# CPU.net
KiCad netlist of a schematic drawn in Altium Designer
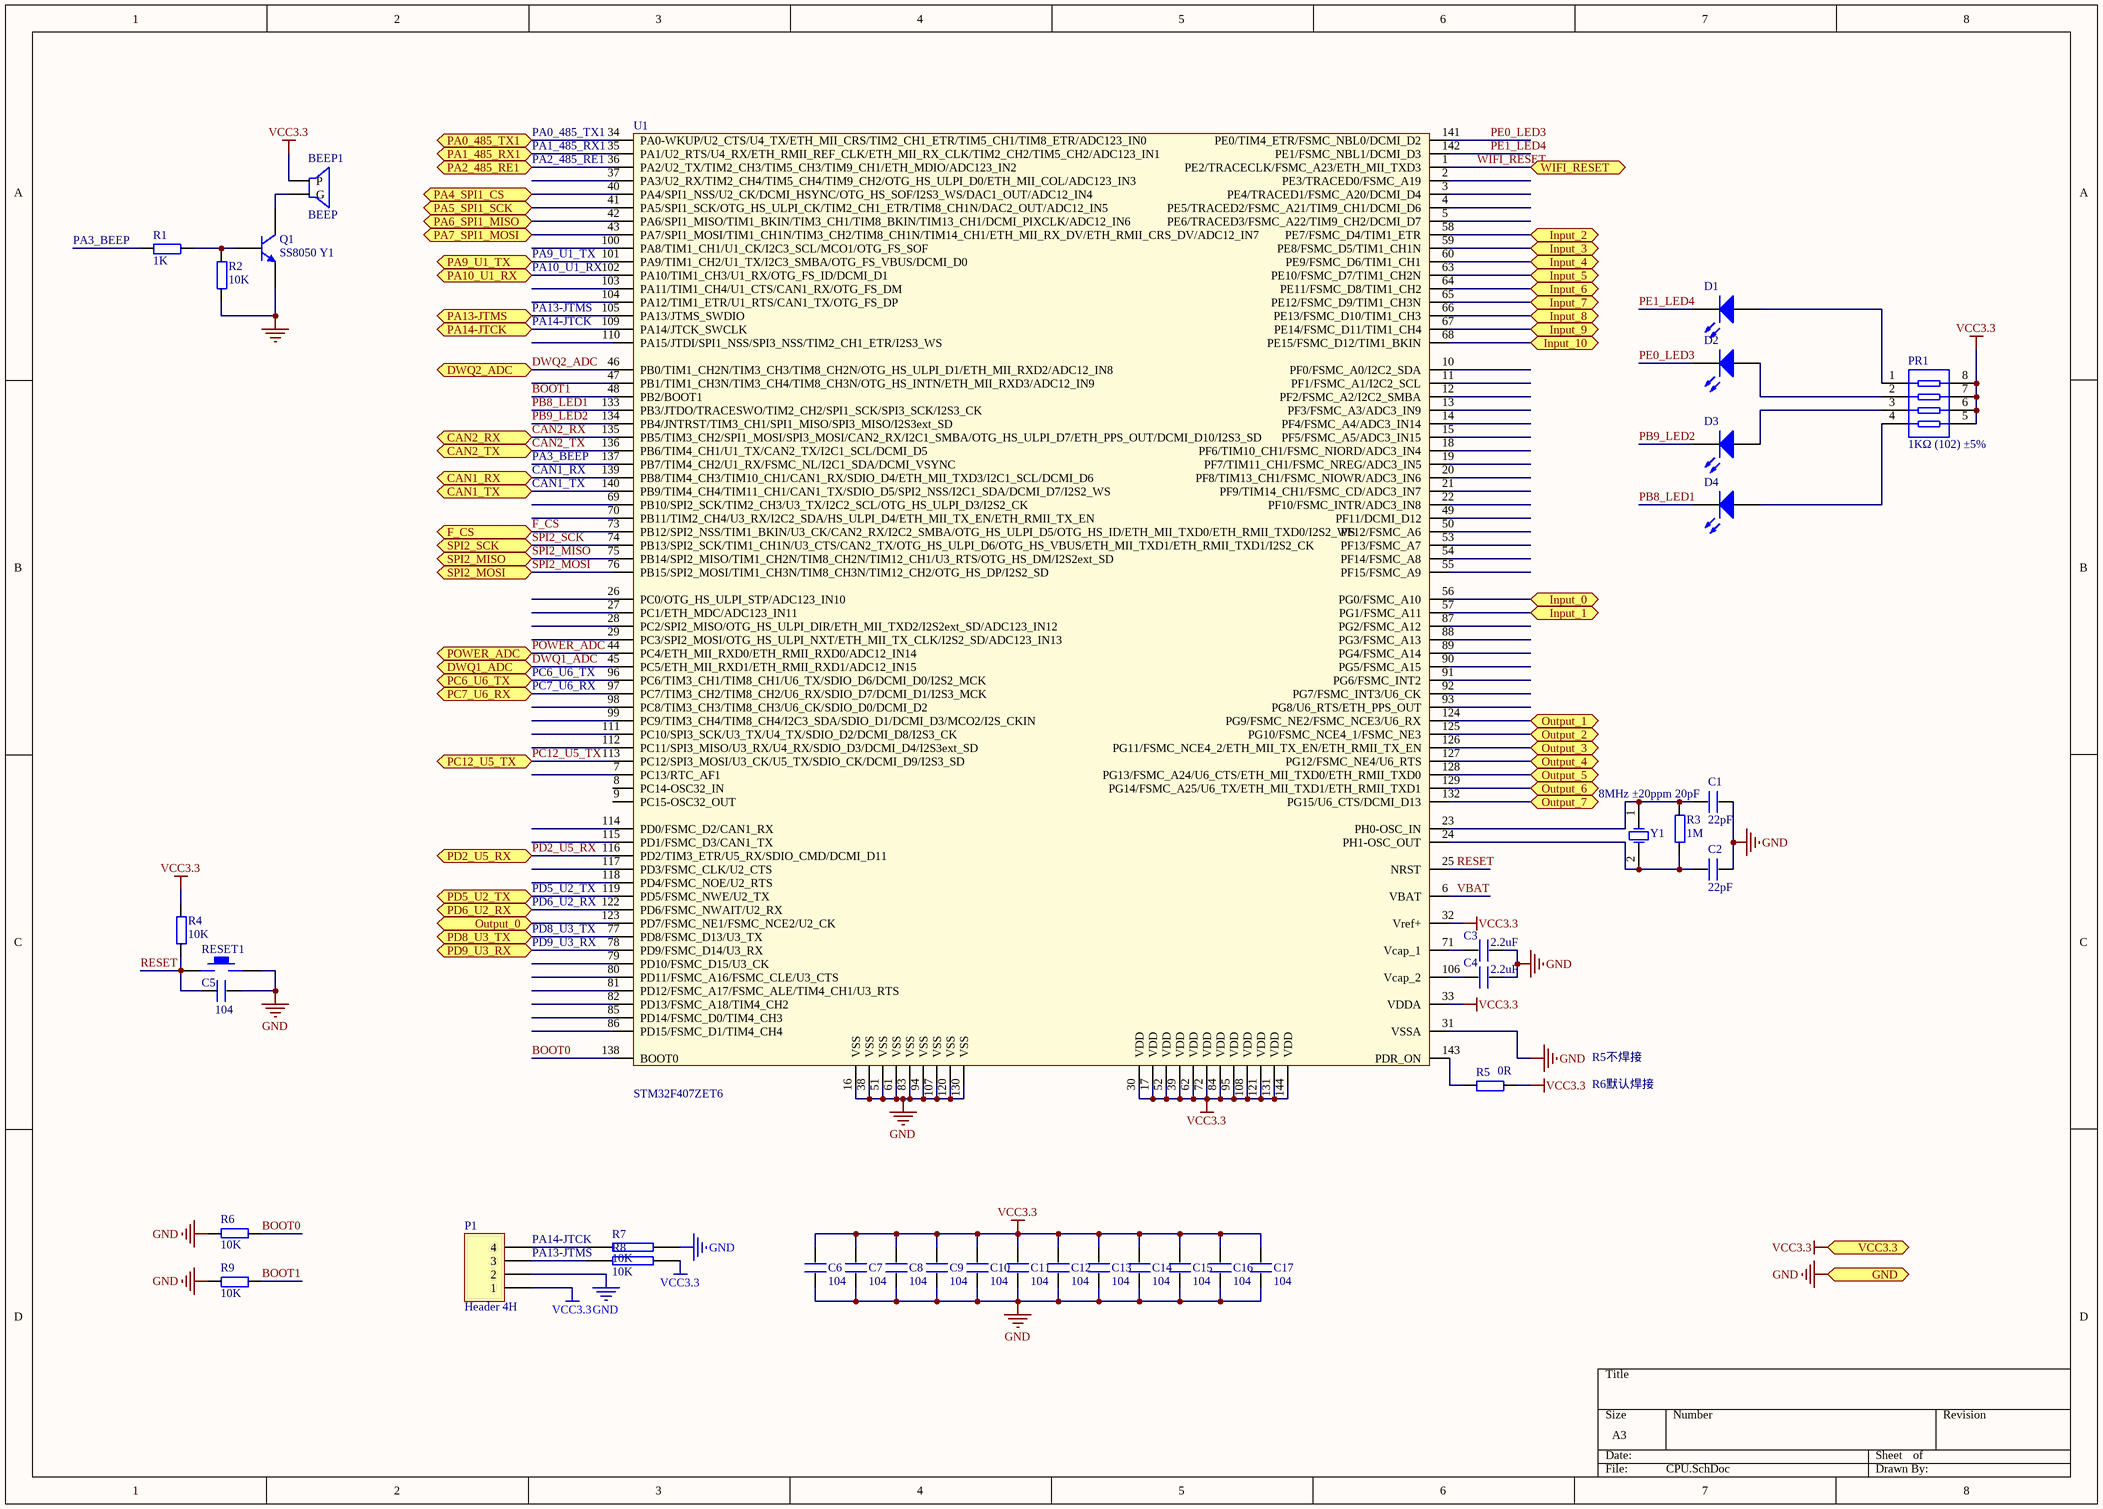
[diagram p0: CPU.SchDoc]

(export (version "E")
  (design (tool "Eeschema 10.0.6"))
  (components
    (comp (ref "BEEP1") (value "BEEP") (footprint "BELL-5") (libsource (lib "WarShip V3_SCH") (part "BEEP")))
    (comp (ref "C1")
      (value "22pF")
      (footprint "0603_C")
      (libsource (lib "Explorer STM32F407封装库") (part "C_3"))
    )
    (comp (ref "C2")
      (value "22pF")
      (footprint "0603_C")
      (libsource (lib "Explorer STM32F407封装库") (part "C_3"))
    )
    (comp (ref "C3")
      (value "2.2uF")
      (footprint "0603_C")
      (libsource (lib "Explorer STM32F407封装库") (part "C"))
    )
    (comp (ref "C4")
      (value "2.2uF")
      (footprint "0603_C")
      (libsource (lib "Explorer STM32F407封装库") (part "C"))
    )
    (comp (ref "C5") (value "104") (footprint "0603_C") (libsource (lib "Explorer STM32F407封装库") (part "C")))
    (comp (ref "C6") (value "104") (footprint "0603_C") (libsource (lib "WarShip V3_SCH") (part "C")))
    (comp (ref "C7") (value "104") (footprint "0603_C") (libsource (lib "WarShip V3_SCH") (part "C")))
    (comp (ref "C8") (value "104") (footprint "0603_C") (libsource (lib "WarShip V3_SCH") (part "C")))
    (comp (ref "C9") (value "104") (footprint "0603_C") (libsource (lib "WarShip V3_SCH") (part "C")))
    (comp (ref "C10") (value "104") (footprint "0603_C") (libsource (lib "WarShip V3_SCH") (part "C")))
    (comp (ref "C11") (value "104") (footprint "0603_C") (libsource (lib "WarShip V3_SCH") (part "C")))
    (comp (ref "C12") (value "104") (footprint "0603_C") (libsource (lib "WarShip V3_SCH") (part "C")))
    (comp (ref "C13") (value "104") (footprint "0603_C") (libsource (lib "WarShip V3_SCH") (part "C")))
    (comp (ref "C14") (value "104") (footprint "0603_C") (libsource (lib "WarShip V3_SCH") (part "C")))
    (comp (ref "C15") (value "104") (footprint "0603_C") (libsource (lib "WarShip V3_SCH") (part "C")))
    (comp (ref "C16") (value "104") (footprint "0603_C") (libsource (lib "WarShip V3_SCH") (part "C")))
    (comp (ref "C17") (value "104") (footprint "0603_C") (libsource (lib "WarShip V3_SCH") (part "C")))
    (comp (ref "D1")
      (value "红灯 0805")
      (footprint "LC-0805_LED_S1")
      (description "Typical INFRARED GaAs LED")
      (fields (field (name "PUBLISHER") "Altium Limited"))
      (libsource (lib "继电器板_1") (part "LED0"))
    )
    (comp (ref "D2")
      (value "红灯 0805")
      (footprint "LC-0805_LED_S1")
      (description "Typical INFRARED GaAs LED")
      (fields (field (name "PUBLISHER") "Altium Limited"))
      (libsource (lib "继电器板_1") (part "LED0"))
    )
    (comp (ref "D3")
      (value "红灯 0805")
      (footprint "LC-0805_LED_S1")
      (description "Typical INFRARED GaAs LED")
      (fields (field (name "PUBLISHER") "Altium Limited"))
      (libsource (lib "继电器板_1") (part "LED0"))
    )
    (comp (ref "D4")
      (value "红灯 0805")
      (footprint "LC-0805_LED_S1")
      (description "Typical INFRARED GaAs LED")
      (fields (field (name "PUBLISHER") "Altium Limited"))
      (libsource (lib "继电器板_1") (part "LED0"))
    )
    (comp (ref "P1")
      (value "Header 4H")
      (footprint "IDE4")
      (description "Header, 4-Pin, Right Angle")
      (fields (field (name "PUBLISHER") "Altium Limited"))
      (libsource (lib "Miscellaneous Connectors") (part "Header 4H"))
    )
    (comp (ref "PR1")
      (value "1KΩ (102) ±5%")
      (footprint "0603_Rx4")
      (description "贴片排阻")
      (libsource (lib "Miscellaneous Devices LC") (part "0603*4  1KΩ (102) 5%"))
    )
    (comp (ref "Q1")
      (value "SS8050 Y1")
      (footprint "SOT-23(SOT-23-3)")
      (description "三极管")
      (libsource (lib "Miscellaneous Devices LC") (part "SOT-23 SS8050 Y1"))
    )
    (comp (ref "R1") (value "1K") (footprint "0603_R") (libsource (lib "WarShip V3_SCH") (part "R")))
    (comp (ref "R2") (value "10K") (footprint "0603_R") (libsource (lib "WarShip V3_SCH") (part "R")))
    (comp (ref "R3") (value "1M") (footprint "0603_R") (libsource (lib "Explorer STM32F407封装库") (part "R")))
    (comp (ref "R4")
      (value "10K")
      (footprint "0603_R")
      (libsource (lib "Explorer STM32F407封装库") (part "R_2"))
    )
    (comp (ref "R5") (value "0R") (footprint "0603_R") (libsource (lib "Explorer STM32F407封装库") (part "R_2")))
    (comp (ref "R6")
      (value "10K")
      (footprint "0603_R")
      (libsource (lib "Explorer STM32F407封装库") (part "R_1"))
    )
    (comp (ref "R7") (value "10K") (footprint "0603_R") (libsource (lib "*") (part "RES2")))
    (comp (ref "R8") (value "10K") (footprint "0603_R") (libsource (lib "*") (part "RES2")))
    (comp (ref "R9")
      (value "10K")
      (footprint "0603_R")
      (libsource (lib "Explorer STM32F407封装库") (part "R_1"))
    )
    (comp (ref "RESET1")
      (value "KEY_M")
      (footprint "SW_PB2_A1")
      (libsource (lib "Explorer STM32F407封装库") (part "KEY_M"))
    )
    (comp (ref "U1")
      (value "STM32F407ZET6")
      (footprint "LQFP-144_20x20x05P")
      (libsource (lib "Explorer STM32F407封装库") (part "STM32F407ZET6"))
    )
    (comp (ref "Y1")
      (value "8MHz ±20ppm 20pF")
      (footprint "SMD-5032_2P")
      (description "贴片晶振")
      (libsource (lib "Miscellaneous Devices LC") (part "SMD-5032_2P 8MHz 20ppm 20pF"))
    )
  )
  (nets
    (net (code "1") (name "/BOOT0") (class "Default")
      (node (ref "R6") (pin "1") (pintype "passive"))
      (node (ref "U1") (pin "138") (pinfunction "BOOT0_138") (pintype "passive"))
    )
    (net (code "2") (name "/BOOT1") (class "Default")
      (node (ref "R9") (pin "2") (pintype "passive"))
      (node (ref "U1") (pin "48") (pinfunction "PB2/BOOT1_48") (pintype "passive"))
    )
    (net (code "3") (name "/CAN1_RX") (class "Default")
      (node (ref "U1") (pin "139") (pinfunction "PB8/TIM4_CH3/TIM10_CH1/CAN1_RX/SDIO_D4/ETH_MII_TXD3/I2C1_SCL/DCMI_D6_139") (pintype "passive"))
    )
    (net (code "4") (name "/CAN1_TX") (class "Default")
      (node (ref "U1") (pin "140") (pinfunction "PB9/TIM4_CH4/TIM11_CH1/CAN1_TX/SDIO_D5/SPI2_NSS/I2C1_SDA/DCMI_D7/I2S2_WS_140") (pintype "passive"))
    )
    (net (code "5") (name "/CAN2_RX") (class "Default")
      (node (ref "U1") (pin "135") (pinfunction "PB5/TIM3_CH2/SPI1_MOSI/SPI3_MOSI/CAN2_RX/I2C1_SMBA/OTG_HS_ULPI_D7/ETH_PPS_OUT/DCMI_D10/I2S3_SD_135") (pintype "passive"))
    )
    (net (code "6") (name "/CAN2_TX") (class "Default")
      (node (ref "U1") (pin "136") (pinfunction "PB6/TIM4_CH1/U1_TX/CAN2_TX/I2C1_SCL/DCMI_D5_136") (pintype "passive"))
    )
    (net (code "7") (name "/DWQ1_ADC") (class "Default")
      (node (ref "U1") (pin "45") (pinfunction "PC5/ETH_MII_RXD1/ETH_RMII_RXD1/ADC12_IN15_45") (pintype "passive"))
    )
    (net (code "8") (name "/DWQ2_ADC") (class "Default")
      (node (ref "U1") (pin "46") (pinfunction "PB0/TIM1_CH2N/TIM3_CH3/TIM8_CH2N/OTG_HS_ULPI_D1/ETH_MII_RXD2/ADC12_IN8_46") (pintype "passive"))
    )
    (net (code "9") (name "/F_CS") (class "Default")
      (node (ref "U1") (pin "73") (pinfunction "PB12/SPI2_NSS/TIM1_BKIN/U3_CK/CAN2_RX/I2C2_SMBA/OTG_HS_ULPI_D5/OTG_HS_ID/ETH_MII_TXD0/ETH_RMII_TXD0/I2S2_WS_73") (pintype "passive"))
    )
    (net (code "10") (name "/Input_0") (class "Default")
      (node (ref "U1") (pin "56") (pinfunction "PG0/FSMC_A10_56") (pintype "passive"))
    )
    (net (code "11") (name "/Input_1") (class "Default")
      (node (ref "U1") (pin "57") (pinfunction "PG1/FSMC_A11_57") (pintype "passive"))
    )
    (net (code "12") (name "/Input_2") (class "Default")
      (node (ref "U1") (pin "58") (pinfunction "PE7/FSMC_D4/TIM1_ETR_58") (pintype "passive"))
    )
    (net (code "13") (name "/Input_3") (class "Default")
      (node (ref "U1") (pin "59") (pinfunction "PE8/FSMC_D5/TIM1_CH1N_59") (pintype "passive"))
    )
    (net (code "14") (name "/Input_4") (class "Default")
      (node (ref "U1") (pin "60") (pinfunction "PE9/FSMC_D6/TIM1_CH1_60") (pintype "passive"))
    )
    (net (code "15") (name "/Input_5") (class "Default")
      (node (ref "U1") (pin "63") (pinfunction "PE10/FSMC_D7/TIM1_CH2N_63") (pintype "passive"))
    )
    (net (code "16") (name "/Input_6") (class "Default")
      (node (ref "U1") (pin "64") (pinfunction "PE11/FSMC_D8/TIM1_CH2_64") (pintype "passive"))
    )
    (net (code "17") (name "/Input_7") (class "Default")
      (node (ref "U1") (pin "65") (pinfunction "PE12/FSMC_D9/TIM1_CH3N_65") (pintype "passive"))
    )
    (net (code "18") (name "/Input_8") (class "Default")
      (node (ref "U1") (pin "66") (pinfunction "PE13/FSMC_D10/TIM1_CH3_66") (pintype "passive"))
    )
    (net (code "19") (name "/Input_9") (class "Default")
      (node (ref "U1") (pin "67") (pinfunction "PE14/FSMC_D11/TIM1_CH4_67") (pintype "passive"))
    )
    (net (code "20") (name "/Input_10") (class "Default")
      (node (ref "U1") (pin "68") (pinfunction "PE15/FSMC_D12/TIM1_BKIN_68") (pintype "passive"))
    )
    (net (code "21") (name "/Output_0") (class "Default")
      (node (ref "U1") (pin "123") (pinfunction "PD7/FSMC_NE1/FSMC_NCE2/U2_CK_123") (pintype "passive"))
    )
    (net (code "22") (name "/Output_1") (class "Default")
      (node (ref "U1") (pin "124") (pinfunction "PG9/FSMC_NE2/FSMC_NCE3/U6_RX_124") (pintype "passive"))
    )
    (net (code "23") (name "/Output_2") (class "Default")
      (node (ref "U1") (pin "125") (pinfunction "PG10/FSMC_NCE4_1/FSMC_NE3_125") (pintype "passive"))
    )
    (net (code "24") (name "/Output_3") (class "Default")
      (node (ref "U1") (pin "126") (pinfunction "PG11/FSMC_NCE4_2/ETH_MII_TX_EN/ETH_RMII_TX_EN_126") (pintype "passive"))
    )
    (net (code "25") (name "/Output_4") (class "Default")
      (node (ref "U1") (pin "127") (pinfunction "PG12/FSMC_NE4/U6_RTS_127") (pintype "passive"))
    )
    (net (code "26") (name "/Output_5") (class "Default")
      (node (ref "U1") (pin "128") (pinfunction "PG13/FSMC_A24/U6_CTS/ETH_MII_TXD0/ETH_RMII_TXD0_128") (pintype "passive"))
    )
    (net (code "27") (name "/Output_6") (class "Default")
      (node (ref "U1") (pin "129") (pinfunction "PG14/FSMC_A25/U6_TX/ETH_MII_TXD1/ETH_RMII_TXD1_129") (pintype "passive"))
    )
    (net (code "28") (name "/Output_7") (class "Default")
      (node (ref "U1") (pin "132") (pinfunction "PG15/U6_CTS/DCMI_D13_132") (pintype "passive"))
    )
    (net (code "29") (name "/PA0_485_TX1") (class "Default")
      (node (ref "U1") (pin "34") (pinfunction "PA0-WKUP/U2_CTS/U4_TX/ETH_MII_CRS/TIM2_CH1_ETR/TIM5_CH1/TIM8_ETR/ADC123_IN0_34") (pintype "passive"))
    )
    (net (code "30") (name "/PA1_485_RX1") (class "Default")
      (node (ref "U1") (pin "35") (pinfunction "PA1/U2_RTS/U4_RX/ETH_RMII_REF_CLK/ETH_MII_RX_CLK/TIM2_CH2/TIM5_CH2/ADC123_IN1_35") (pintype "passive"))
    )
    (net (code "31") (name "/PA2_485_RE1") (class "Default")
      (node (ref "U1") (pin "36") (pinfunction "PA2/U2_TX/TIM2_CH3/TIM5_CH3/TIM9_CH1/ETH_MDIO/ADC123_IN2_36") (pintype "passive"))
    )
    (net (code "32") (name "/PA3_BEEP") (class "Default")
      (node (ref "R1") (pin "1") (pintype "passive"))
      (node (ref "U1") (pin "137") (pinfunction "PB7/TIM4_CH2/U1_RX/FSMC_NL/I2C1_SDA/DCMI_VSYNC_137") (pintype "passive"))
    )
    (net (code "33") (name "/PA4_SPI1_CS") (class "Default")
      (node (ref "U1") (pin "40") (pinfunction "PA4/SPI1_NSS/U2_CK/DCMI_HSYNC/OTG_HS_SOF/I2S3_WS/DAC1_OUT/ADC12_IN4_40") (pintype "passive"))
    )
    (net (code "34") (name "/PA5_SPI1_SCK") (class "Default")
      (node (ref "U1") (pin "41") (pinfunction "PA5/SPI1_SCK/OTG_HS_ULPI_CK/TIM2_CH1_ETR/TIM8_CH1N/DAC2_OUT/ADC12_IN5_41") (pintype "passive"))
    )
    (net (code "35") (name "/PA6_SPI1_MISO") (class "Default")
      (node (ref "U1") (pin "42") (pinfunction "PA6/SPI1_MISO/TIM1_BKIN/TIM3_CH1/TIM8_BKIN/TIM13_CH1/DCMI_PIXCLK/ADC12_IN6_42") (pintype "passive"))
    )
    (net (code "36") (name "/PA7_SPI1_MOSI") (class "Default")
      (node (ref "U1") (pin "43") (pinfunction "PA7/SPI1_MOSI/TIM1_CH1N/TIM3_CH2/TIM8_CH1N/TIM14_CH1/ETH_MII_RX_DV/ETH_RMII_CRS_DV/ADC12_IN7_43") (pintype "passive"))
    )
    (net (code "37") (name "/PA9_U1_TX") (class "Default")
      (node (ref "U1") (pin "101") (pinfunction "PA9/TIM1_CH2/U1_TX/I2C3_SMBA/OTG_FS_VBUS/DCMI_D0_101") (pintype "passive"))
    )
    (net (code "38") (name "/PA10_U1_RX") (class "Default")
      (node (ref "U1") (pin "102") (pinfunction "PA10/TIM1_CH3/U1_RX/OTG_FS_ID/DCMI_D1_102") (pintype "passive"))
    )
    (net (code "39") (name "/PA13-JTMS") (class "Default")
      (node (ref "P1") (pin "3") (pinfunction "3_3") (pintype "passive"))
      (node (ref "R8") (pin "2") (pinfunction "2_2") (pintype "passive"))
      (node (ref "U1") (pin "105") (pinfunction "PA13/JTMS_SWDIO_105") (pintype "passive"))
    )
    (net (code "40") (name "/PA14-JTCK") (class "Default")
      (node (ref "P1") (pin "4") (pinfunction "4_4") (pintype "passive"))
      (node (ref "R7") (pin "2") (pinfunction "2_2") (pintype "passive"))
      (node (ref "U1") (pin "109") (pinfunction "PA14/JTCK_SWCLK_109") (pintype "passive"))
    )
    (net (code "41") (name "/PB8_LED1") (class "Default")
      (node (ref "D4") (pin "K") (pinfunction "K_K") (pintype "passive"))
      (node (ref "U1") (pin "133") (pinfunction "PB3/JTDO/TRACESWO/TIM2_CH2/SPI1_SCK/SPI3_SCK/I2S3_CK_133") (pintype "passive"))
    )
    (net (code "42") (name "/PB9_LED2") (class "Default")
      (node (ref "D3") (pin "K") (pinfunction "K_K") (pintype "passive"))
      (node (ref "U1") (pin "134") (pinfunction "PB4/JNTRST/TIM3_CH1/SPI1_MISO/SPI3_MISO/I2S3ext_SD_134") (pintype "passive"))
    )
    (net (code "43") (name "/PC6_U6_TX") (class "Default")
      (node (ref "U1") (pin "96") (pinfunction "PC6/TIM3_CH1/TIM8_CH1/U6_TX/SDIO_D6/DCMI_D0/I2S2_MCK_96") (pintype "passive"))
    )
    (net (code "44") (name "/PC7_U6_RX") (class "Default")
      (node (ref "U1") (pin "97") (pinfunction "PC7/TIM3_CH2/TIM8_CH2/U6_RX/SDIO_D7/DCMI_D1/I2S3_MCK_97") (pintype "passive"))
    )
    (net (code "45") (name "/PC12_U5_TX") (class "Default")
      (node (ref "U1") (pin "113") (pinfunction "PC12/SPI3_MOSI/U3_CK/U5_TX/SDIO_CK/DCMI_D9/I2S3_SD_113") (pintype "passive"))
    )
    (net (code "46") (name "/PD2_U5_RX") (class "Default")
      (node (ref "U1") (pin "116") (pinfunction "PD2/TIM3_ETR/U5_RX/SDIO_CMD/DCMI_D11_116") (pintype "passive"))
    )
    (net (code "47") (name "/PD5_U2_TX") (class "Default")
      (node (ref "U1") (pin "119") (pinfunction "PD5/FSMC_NWE/U2_TX_119") (pintype "passive"))
    )
    (net (code "48") (name "/PD6_U2_RX") (class "Default")
      (node (ref "U1") (pin "122") (pinfunction "PD6/FSMC_NWAIT/U2_RX_122") (pintype "passive"))
    )
    (net (code "49") (name "/PD8_U3_TX") (class "Default")
      (node (ref "U1") (pin "77") (pinfunction "PD8/FSMC_D13/U3_TX_77") (pintype "passive"))
    )
    (net (code "50") (name "/PD9_U3_RX") (class "Default")
      (node (ref "U1") (pin "78") (pinfunction "PD9/FSMC_D14/U3_RX_78") (pintype "passive"))
    )
    (net (code "51") (name "/PE0_LED3") (class "Default")
      (node (ref "D2") (pin "K") (pinfunction "K_K") (pintype "passive"))
      (node (ref "U1") (pin "141") (pinfunction "PE0/TIM4_ETR/FSMC_NBL0/DCMI_D2_141") (pintype "passive"))
    )
    (net (code "52") (name "/PE1_LED4") (class "Default")
      (node (ref "D1") (pin "K") (pinfunction "K_K") (pintype "passive"))
      (node (ref "U1") (pin "142") (pinfunction "PE1/FSMC_NBL1/DCMI_D3_142") (pintype "passive"))
    )
    (net (code "53") (name "/POWER_ADC") (class "Default")
      (node (ref "U1") (pin "44") (pinfunction "PC4/ETH_MII_RXD0/ETH_RMII_RXD0/ADC12_IN14_44") (pintype "passive"))
    )
    (net (code "54") (name "/RESET") (class "Default")
      (node (ref "C5") (pin "1") (pintype "passive"))
      (node (ref "R4") (pin "1") (pintype "passive"))
      (node (ref "RESET1") (pin "1") (pinfunction "1_1") (pintype "passive"))
      (node (ref "U1") (pin "25") (pinfunction "NRST_25") (pintype "passive"))
    )
    (net (code "55") (name "/SPI2_MISO") (class "Default")
      (node (ref "U1") (pin "75") (pinfunction "PB14/SPI2_MISO/TIM1_CH2N/TIM8_CH2N/TIM12_CH1/U3_RTS/OTG_HS_DM/I2S2ext_SD_75") (pintype "passive"))
    )
    (net (code "56") (name "/SPI2_MOSI") (class "Default")
      (node (ref "U1") (pin "76") (pinfunction "PB15/SPI2_MOSI/TIM1_CH3N/TIM8_CH3N/TIM12_CH2/OTG_HS_DP/I2S2_SD_76") (pintype "passive"))
    )
    (net (code "57") (name "/SPI2_SCK") (class "Default")
      (node (ref "U1") (pin "74") (pinfunction "PB13/SPI2_SCK/TIM1_CH1N/U3_CTS/CAN2_TX/OTG_HS_ULPI_D6/OTG_HS_VBUS/ETH_MII_TXD1/ETH_RMII_TXD1/I2S2_CK_74") (pintype "passive"))
    )
    (net (code "58") (name "/VBAT") (class "Default")
      (node (ref "U1") (pin "6") (pinfunction "VBAT_6") (pintype "passive"))
    )
    (net (code "59") (name "/WIFI_RESET") (class "Default")
      (node (ref "U1") (pin "1") (pinfunction "PE2/TRACECLK/FSMC_A23/ETH_MII_TXD3_1") (pintype "passive"))
    )
    (net (code "60") (name "GND") (class "Default")
      (node (ref "C1") (pin "1") (pintype "passive"))
      (node (ref "C10") (pin "1") (pintype "passive"))
      (node (ref "C11") (pin "1") (pintype "passive"))
      (node (ref "C12") (pin "1") (pintype "passive"))
      (node (ref "C13") (pin "1") (pintype "passive"))
      (node (ref "C14") (pin "1") (pintype "passive"))
      (node (ref "C15") (pin "1") (pintype "passive"))
      (node (ref "C16") (pin "1") (pintype "passive"))
      (node (ref "C17") (pin "1") (pintype "passive"))
      (node (ref "C2") (pin "1") (pintype "passive"))
      (node (ref "C3") (pin "2") (pintype "passive"))
      (node (ref "C4") (pin "2") (pintype "passive"))
      (node (ref "C5") (pin "2") (pintype "passive"))
      (node (ref "C6") (pin "1") (pintype "passive"))
      (node (ref "C7") (pin "1") (pintype "passive"))
      (node (ref "C8") (pin "1") (pintype "passive"))
      (node (ref "C9") (pin "1") (pintype "passive"))
      (node (ref "P1") (pin "2") (pinfunction "2_2") (pintype "passive"))
      (node (ref "Q1") (pin "2") (pinfunction "E_2") (pintype "passive"))
      (node (ref "R2") (pin "1") (pintype "passive"))
      (node (ref "R6") (pin "2") (pintype "passive"))
      (node (ref "R7") (pin "1") (pinfunction "1_1") (pintype "passive"))
      (node (ref "R9") (pin "1") (pintype "passive"))
      (node (ref "RESET1") (pin "2") (pinfunction "2_2") (pintype "passive"))
      (node (ref "U1") (pin "107") (pinfunction "VSS_107") (pintype "passive"))
      (node (ref "U1") (pin "120") (pinfunction "VSS_120") (pintype "passive"))
      (node (ref "U1") (pin "130") (pinfunction "VSS_130") (pintype "passive"))
      (node (ref "U1") (pin "16") (pinfunction "VSS_16") (pintype "passive"))
      (node (ref "U1") (pin "31") (pinfunction "VSSA_31") (pintype "passive"))
      (node (ref "U1") (pin "38") (pinfunction "VSS_38") (pintype "passive"))
      (node (ref "U1") (pin "51") (pinfunction "VSS_51") (pintype "passive"))
      (node (ref "U1") (pin "61") (pinfunction "VSS_61") (pintype "passive"))
      (node (ref "U1") (pin "83") (pinfunction "VSS_83") (pintype "passive"))
      (node (ref "U1") (pin "94") (pinfunction "VSS_94") (pintype "passive"))
    )
    (net (code "61") (name "Net-(BEEP1-G)") (class "Default")
      (node (ref "BEEP1") (pin "2") (pinfunction "G_2") (pintype "passive"))
      (node (ref "Q1") (pin "3") (pinfunction "C_3") (pintype "passive"))
    )
    (net (code "62") (name "Net-(D1-PadA)") (class "Default")
      (node (ref "D1") (pin "A") (pinfunction "A_A") (pintype "passive"))
      (node (ref "PR1") (pin "1") (pinfunction "1_1") (pintype "passive"))
    )
    (net (code "63") (name "Net-(D2-PadA)") (class "Default")
      (node (ref "D2") (pin "A") (pinfunction "A_A") (pintype "passive"))
      (node (ref "PR1") (pin "2") (pinfunction "2_2") (pintype "passive"))
    )
    (net (code "64") (name "Net-(D3-PadA)") (class "Default")
      (node (ref "D3") (pin "A") (pinfunction "A_A") (pintype "passive"))
      (node (ref "PR1") (pin "3") (pinfunction "3_3") (pintype "passive"))
    )
    (net (code "65") (name "Net-(D4-PadA)") (class "Default")
      (node (ref "D4") (pin "A") (pinfunction "A_A") (pintype "passive"))
      (node (ref "PR1") (pin "4") (pinfunction "4_4") (pintype "passive"))
    )
    (net (code "66") (name "Net-(Q1-B)") (class "Default")
      (node (ref "Q1") (pin "1") (pinfunction "B_1") (pintype "passive"))
      (node (ref "R1") (pin "2") (pintype "passive"))
      (node (ref "R2") (pin "2") (pintype "passive"))
    )
    (net (code "67") (name "Net-(U1-PDR_ON)") (class "Default")
      (node (ref "R5") (pin "1") (pintype "passive"))
      (node (ref "U1") (pin "143") (pinfunction "PDR_ON_143") (pintype "passive"))
    )
    (net (code "68") (name "Net-(U1-PH0-OSC_IN)") (class "Default")
      (node (ref "C1") (pin "2") (pintype "passive"))
      (node (ref "R3") (pin "2") (pintype "passive"))
      (node (ref "U1") (pin "23") (pinfunction "PH0-OSC_IN_23") (pintype "passive"))
      (node (ref "Y1") (pin "1") (pinfunction "OSC1_1") (pintype "passive"))
    )
    (net (code "69") (name "Net-(U1-PH1-OSC_OUT)") (class "Default")
      (node (ref "C2") (pin "2") (pintype "passive"))
      (node (ref "R3") (pin "1") (pintype "passive"))
      (node (ref "U1") (pin "24") (pinfunction "PH1-OSC_OUT_24") (pintype "passive"))
      (node (ref "Y1") (pin "2") (pinfunction "OSC2_2") (pintype "passive"))
    )
    (net (code "70") (name "Net-(U1-Vcap_1)") (class "Default")
      (node (ref "C3") (pin "1") (pintype "passive"))
      (node (ref "U1") (pin "71") (pinfunction "Vcap_1_71") (pintype "passive"))
    )
    (net (code "71") (name "Net-(U1-Vcap_2)") (class "Default")
      (node (ref "C4") (pin "1") (pintype "passive"))
      (node (ref "U1") (pin "106") (pinfunction "Vcap_2_106") (pintype "passive"))
    )
    (net (code "72") (name "VCC3.3") (class "Default")
      (node (ref "BEEP1") (pin "1") (pinfunction "P_1") (pintype "passive"))
      (node (ref "C10") (pin "2") (pintype "passive"))
      (node (ref "C11") (pin "2") (pintype "passive"))
      (node (ref "C12") (pin "2") (pintype "passive"))
      (node (ref "C13") (pin "2") (pintype "passive"))
      (node (ref "C14") (pin "2") (pintype "passive"))
      (node (ref "C15") (pin "2") (pintype "passive"))
      (node (ref "C16") (pin "2") (pintype "passive"))
      (node (ref "C17") (pin "2") (pintype "passive"))
      (node (ref "C6") (pin "2") (pintype "passive"))
      (node (ref "C7") (pin "2") (pintype "passive"))
      (node (ref "C8") (pin "2") (pintype "passive"))
      (node (ref "C9") (pin "2") (pintype "passive"))
      (node (ref "P1") (pin "1") (pinfunction "1_1") (pintype "passive"))
      (node (ref "PR1") (pin "5") (pinfunction "5_5") (pintype "passive"))
      (node (ref "PR1") (pin "6") (pinfunction "6_6") (pintype "passive"))
      (node (ref "PR1") (pin "7") (pinfunction "7_7") (pintype "passive"))
      (node (ref "PR1") (pin "8") (pinfunction "8_8") (pintype "passive"))
      (node (ref "R4") (pin "2") (pintype "passive"))
      (node (ref "R5") (pin "2") (pintype "passive"))
      (node (ref "R8") (pin "1") (pinfunction "1_1") (pintype "passive"))
      (node (ref "U1") (pin "108") (pinfunction "VDD_108") (pintype "passive"))
      (node (ref "U1") (pin "121") (pinfunction "VDD_121") (pintype "passive"))
      (node (ref "U1") (pin "131") (pinfunction "VDD_131") (pintype "passive"))
      (node (ref "U1") (pin "144") (pinfunction "VDD_144") (pintype "passive"))
      (node (ref "U1") (pin "17") (pinfunction "VDD_17") (pintype "passive"))
      (node (ref "U1") (pin "30") (pinfunction "VDD_30") (pintype "passive"))
      (node (ref "U1") (pin "32") (pinfunction "Vref+_32") (pintype "passive"))
      (node (ref "U1") (pin "33") (pinfunction "VDDA_33") (pintype "passive"))
      (node (ref "U1") (pin "39") (pinfunction "VDD_39") (pintype "passive"))
      (node (ref "U1") (pin "52") (pinfunction "VDD_52") (pintype "passive"))
      (node (ref "U1") (pin "62") (pinfunction "VDD_62") (pintype "passive"))
      (node (ref "U1") (pin "72") (pinfunction "VDD_72") (pintype "passive"))
      (node (ref "U1") (pin "84") (pinfunction "VDD_84") (pintype "passive"))
      (node (ref "U1") (pin "95") (pinfunction "VDD_95") (pintype "passive"))
    )
    (net (code "73") (name "unconnected-(U1-PA3{slash}U2_RX{slash}TIM2_CH4{slash}TIM5_CH4{slash}TIM9_CH2{slash}OTG_HS_ULPI_D0{slash}ETH_MII_COL{slash}ADC123_IN3-Pad37)") (class "Default")
      (node (ref "U1") (pin "37") (pinfunction "PA3/U2_RX/TIM2_CH4/TIM5_CH4/TIM9_CH2/OTG_HS_ULPI_D0/ETH_MII_COL/ADC123_IN3_37") (pintype "passive"))
    )
    (net (code "74") (name "unconnected-(U1-PA8{slash}TIM1_CH1{slash}U1_CK{slash}I2C3_SCL{slash}MCO1{slash}OTG_FS_SOF-Pad100)") (class "Default")
      (node (ref "U1") (pin "100") (pinfunction "PA8/TIM1_CH1/U1_CK/I2C3_SCL/MCO1/OTG_FS_SOF_100") (pintype "passive"))
    )
    (net (code "75") (name "unconnected-(U1-PA11{slash}TIM1_CH4{slash}U1_CTS{slash}CAN1_RX{slash}OTG_FS_DM-Pad103)") (class "Default")
      (node (ref "U1") (pin "103") (pinfunction "PA11/TIM1_CH4/U1_CTS/CAN1_RX/OTG_FS_DM_103") (pintype "passive"))
    )
    (net (code "76") (name "unconnected-(U1-PA12{slash}TIM1_ETR{slash}U1_RTS{slash}CAN1_TX{slash}OTG_FS_DP-Pad104)") (class "Default")
      (node (ref "U1") (pin "104") (pinfunction "PA12/TIM1_ETR/U1_RTS/CAN1_TX/OTG_FS_DP_104") (pintype "passive"))
    )
    (net (code "77") (name "unconnected-(U1-PA15{slash}JTDI{slash}SPI1_NSS{slash}SPI3_NSS{slash}TIM2_CH1_ETR{slash}I2S3_WS-Pad110)") (class "Default")
      (node (ref "U1") (pin "110") (pinfunction "PA15/JTDI/SPI1_NSS/SPI3_NSS/TIM2_CH1_ETR/I2S3_WS_110") (pintype "passive"))
    )
    (net (code "78") (name "unconnected-(U1-PB1{slash}TIM1_CH3N{slash}TIM3_CH4{slash}TIM8_CH3N{slash}OTG_HS_INTN{slash}ETH_MII_RXD3{slash}ADC12_IN9-Pad47)") (class "Default")
      (node (ref "U1") (pin "47") (pinfunction "PB1/TIM1_CH3N/TIM3_CH4/TIM8_CH3N/OTG_HS_INTN/ETH_MII_RXD3/ADC12_IN9_47") (pintype "passive"))
    )
    (net (code "79") (name "unconnected-(U1-PB10{slash}SPI2_SCK{slash}TIM2_CH3{slash}U3_TX{slash}I2C2_SCL{slash}OTG_HS_ULPI_D3{slash}I2S2_CK-Pad69)") (class "Default")
      (node (ref "U1") (pin "69") (pinfunction "PB10/SPI2_SCK/TIM2_CH3/U3_TX/I2C2_SCL/OTG_HS_ULPI_D3/I2S2_CK_69") (pintype "passive"))
    )
    (net (code "80") (name "unconnected-(U1-PB11{slash}TIM2_CH4{slash}U3_RX{slash}I2C2_SDA{slash}HS_ULPI_D4{slash}ETH_MII_TX_EN{slash}ETH_RMII_TX_EN-Pad70)") (class "Default")
      (node (ref "U1") (pin "70") (pinfunction "PB11/TIM2_CH4/U3_RX/I2C2_SDA/HS_ULPI_D4/ETH_MII_TX_EN/ETH_RMII_TX_EN_70") (pintype "passive"))
    )
    (net (code "81") (name "unconnected-(U1-PC0{slash}OTG_HS_ULPI_STP{slash}ADC123_IN10-Pad26)") (class "Default")
      (node (ref "U1") (pin "26") (pinfunction "PC0/OTG_HS_ULPI_STP/ADC123_IN10_26") (pintype "passive"))
    )
    (net (code "82") (name "unconnected-(U1-PC1{slash}ETH_MDC{slash}ADC123_IN11-Pad27)") (class "Default")
      (node (ref "U1") (pin "27") (pinfunction "PC1/ETH_MDC/ADC123_IN11_27") (pintype "passive"))
    )
    (net (code "83") (name "unconnected-(U1-PC2{slash}SPI2_MISO{slash}OTG_HS_ULPI_DIR{slash}ETH_MII_TXD2{slash}I2S2ext_SD{slash}ADC123_IN12-Pad28)") (class "Default")
      (node (ref "U1") (pin "28") (pinfunction "PC2/SPI2_MISO/OTG_HS_ULPI_DIR/ETH_MII_TXD2/I2S2ext_SD/ADC123_IN12_28") (pintype "passive"))
    )
    (net (code "84") (name "unconnected-(U1-PC3{slash}SPI2_MOSI{slash}OTG_HS_ULPI_NXT{slash}ETH_MII_TX_CLK{slash}I2S2_SD{slash}ADC123_IN13-Pad29)") (class "Default")
      (node (ref "U1") (pin "29") (pinfunction "PC3/SPI2_MOSI/OTG_HS_ULPI_NXT/ETH_MII_TX_CLK/I2S2_SD/ADC123_IN13_29") (pintype "passive"))
    )
    (net (code "85") (name "unconnected-(U1-PC8{slash}TIM3_CH3{slash}TIM8_CH3{slash}U6_CK{slash}SDIO_D0{slash}DCMI_D2-Pad98)") (class "Default")
      (node (ref "U1") (pin "98") (pinfunction "PC8/TIM3_CH3/TIM8_CH3/U6_CK/SDIO_D0/DCMI_D2_98") (pintype "passive"))
    )
    (net (code "86") (name "unconnected-(U1-PC9{slash}TIM3_CH4{slash}TIM8_CH4{slash}I2C3_SDA{slash}SDIO_D1{slash}DCMI_D3{slash}MCO2{slash}I2S_CKIN-Pad99)") (class "Default")
      (node (ref "U1") (pin "99") (pinfunction "PC9/TIM3_CH4/TIM8_CH4/I2C3_SDA/SDIO_D1/DCMI_D3/MCO2/I2S_CKIN_99") (pintype "passive"))
    )
    (net (code "87") (name "unconnected-(U1-PC10{slash}SPI3_SCK{slash}U3_TX{slash}U4_TX{slash}SDIO_D2{slash}DCMI_D8{slash}I2S3_CK-Pad111)") (class "Default")
      (node (ref "U1") (pin "111") (pinfunction "PC10/SPI3_SCK/U3_TX/U4_TX/SDIO_D2/DCMI_D8/I2S3_CK_111") (pintype "passive"))
    )
    (net (code "88") (name "unconnected-(U1-PC11{slash}SPI3_MISO{slash}U3_RX{slash}U4_RX{slash}SDIO_D3{slash}DCMI_D4{slash}I2S3ext_SD-Pad112)") (class "Default")
      (node (ref "U1") (pin "112") (pinfunction "PC11/SPI3_MISO/U3_RX/U4_RX/SDIO_D3/DCMI_D4/I2S3ext_SD_112") (pintype "passive"))
    )
    (net (code "89") (name "unconnected-(U1-PC13{slash}RTC_AF1-Pad7)") (class "Default")
      (node (ref "U1") (pin "7") (pinfunction "PC13/RTC_AF1_7") (pintype "passive"))
    )
    (net (code "90") (name "unconnected-(U1-PC14-OSC32_IN-Pad8)") (class "Default")
      (node (ref "U1") (pin "8") (pinfunction "PC14-OSC32_IN_8") (pintype "passive"))
    )
    (net (code "91") (name "unconnected-(U1-PC15-OSC32_OUT-Pad9)") (class "Default")
      (node (ref "U1") (pin "9") (pinfunction "PC15-OSC32_OUT_9") (pintype "passive"))
    )
    (net (code "92") (name "unconnected-(U1-PD0{slash}FSMC_D2{slash}CAN1_RX-Pad114)") (class "Default")
      (node (ref "U1") (pin "114") (pinfunction "PD0/FSMC_D2/CAN1_RX_114") (pintype "passive"))
    )
    (net (code "93") (name "unconnected-(U1-PD1{slash}FSMC_D3{slash}CAN1_TX-Pad115)") (class "Default")
      (node (ref "U1") (pin "115") (pinfunction "PD1/FSMC_D3/CAN1_TX_115") (pintype "passive"))
    )
    (net (code "94") (name "unconnected-(U1-PD3{slash}FSMC_CLK{slash}U2_CTS-Pad117)") (class "Default")
      (node (ref "U1") (pin "117") (pinfunction "PD3/FSMC_CLK/U2_CTS_117") (pintype "passive"))
    )
    (net (code "95") (name "unconnected-(U1-PD4{slash}FSMC_NOE{slash}U2_RTS-Pad118)") (class "Default")
      (node (ref "U1") (pin "118") (pinfunction "PD4/FSMC_NOE/U2_RTS_118") (pintype "passive"))
    )
    (net (code "96") (name "unconnected-(U1-PD10{slash}FSMC_D15{slash}U3_CK-Pad79)") (class "Default")
      (node (ref "U1") (pin "79") (pinfunction "PD10/FSMC_D15/U3_CK_79") (pintype "passive"))
    )
    (net (code "97") (name "unconnected-(U1-PD11{slash}FSMC_A16{slash}FSMC_CLE{slash}U3_CTS-Pad80)") (class "Default")
      (node (ref "U1") (pin "80") (pinfunction "PD11/FSMC_A16/FSMC_CLE/U3_CTS_80") (pintype "passive"))
    )
    (net (code "98") (name "unconnected-(U1-PD12{slash}FSMC_A17{slash}FSMC_ALE{slash}TIM4_CH1{slash}U3_RTS-Pad81)") (class "Default")
      (node (ref "U1") (pin "81") (pinfunction "PD12/FSMC_A17/FSMC_ALE/TIM4_CH1/U3_RTS_81") (pintype "passive"))
    )
    (net (code "99") (name "unconnected-(U1-PD13{slash}FSMC_A18{slash}TIM4_CH2-Pad82)") (class "Default")
      (node (ref "U1") (pin "82") (pinfunction "PD13/FSMC_A18/TIM4_CH2_82") (pintype "passive"))
    )
    (net (code "100") (name "unconnected-(U1-PD14{slash}FSMC_D0{slash}TIM4_CH3-Pad85)") (class "Default")
      (node (ref "U1") (pin "85") (pinfunction "PD14/FSMC_D0/TIM4_CH3_85") (pintype "passive"))
    )
    (net (code "101") (name "unconnected-(U1-PD15{slash}FSMC_D1{slash}TIM4_CH4-Pad86)") (class "Default")
      (node (ref "U1") (pin "86") (pinfunction "PD15/FSMC_D1/TIM4_CH4_86") (pintype "passive"))
    )
    (net (code "102") (name "unconnected-(U1-PE3{slash}TRACED0{slash}FSMC_A19-Pad2)") (class "Default")
      (node (ref "U1") (pin "2") (pinfunction "PE3/TRACED0/FSMC_A19_2") (pintype "passive"))
    )
    (net (code "103") (name "unconnected-(U1-PE4{slash}TRACED1{slash}FSMC_A20{slash}DCMI_D4-Pad3)") (class "Default")
      (node (ref "U1") (pin "3") (pinfunction "PE4/TRACED1/FSMC_A20/DCMI_D4_3") (pintype "passive"))
    )
    (net (code "104") (name "unconnected-(U1-PE5{slash}TRACED2{slash}FSMC_A21{slash}TIM9_CH1{slash}DCMI_D6-Pad4)") (class "Default")
      (node (ref "U1") (pin "4") (pinfunction "PE5/TRACED2/FSMC_A21/TIM9_CH1/DCMI_D6_4") (pintype "passive"))
    )
    (net (code "105") (name "unconnected-(U1-PE6{slash}TRACED3{slash}FSMC_A22{slash}TIM9_CH2{slash}DCMI_D7-Pad5)") (class "Default")
      (node (ref "U1") (pin "5") (pinfunction "PE6/TRACED3/FSMC_A22/TIM9_CH2/DCMI_D7_5") (pintype "passive"))
    )
    (net (code "106") (name "unconnected-(U1-PF0{slash}FSMC_A0{slash}I2C2_SDA-Pad10)") (class "Default")
      (node (ref "U1") (pin "10") (pinfunction "PF0/FSMC_A0/I2C2_SDA_10") (pintype "passive"))
    )
    (net (code "107") (name "unconnected-(U1-PF1{slash}FSMC_A1{slash}I2C2_SCL-Pad11)") (class "Default")
      (node (ref "U1") (pin "11") (pinfunction "PF1/FSMC_A1/I2C2_SCL_11") (pintype "passive"))
    )
    (net (code "108") (name "unconnected-(U1-PF2{slash}FSMC_A2{slash}I2C2_SMBA-Pad12)") (class "Default")
      (node (ref "U1") (pin "12") (pinfunction "PF2/FSMC_A2/I2C2_SMBA_12") (pintype "passive"))
    )
    (net (code "109") (name "unconnected-(U1-PF3{slash}FSMC_A3{slash}ADC3_IN9-Pad13)") (class "Default")
      (node (ref "U1") (pin "13") (pinfunction "PF3/FSMC_A3/ADC3_IN9_13") (pintype "passive"))
    )
    (net (code "110") (name "unconnected-(U1-PF4{slash}FSMC_A4{slash}ADC3_IN14-Pad14)") (class "Default")
      (node (ref "U1") (pin "14") (pinfunction "PF4/FSMC_A4/ADC3_IN14_14") (pintype "passive"))
    )
    (net (code "111") (name "unconnected-(U1-PF5{slash}FSMC_A5{slash}ADC3_IN15-Pad15)") (class "Default")
      (node (ref "U1") (pin "15") (pinfunction "PF5/FSMC_A5/ADC3_IN15_15") (pintype "passive"))
    )
    (net (code "112") (name "unconnected-(U1-PF6{slash}TIM10_CH1{slash}FSMC_NIORD{slash}ADC3_IN4-Pad18)") (class "Default")
      (node (ref "U1") (pin "18") (pinfunction "PF6/TIM10_CH1/FSMC_NIORD/ADC3_IN4_18") (pintype "passive"))
    )
    (net (code "113") (name "unconnected-(U1-PF7{slash}TIM11_CH1{slash}FSMC_NREG{slash}ADC3_IN5-Pad19)") (class "Default")
      (node (ref "U1") (pin "19") (pinfunction "PF7/TIM11_CH1/FSMC_NREG/ADC3_IN5_19") (pintype "passive"))
    )
    (net (code "114") (name "unconnected-(U1-PF8{slash}TIM13_CH1{slash}FSMC_NIOWR{slash}ADC3_IN6-Pad20)") (class "Default")
      (node (ref "U1") (pin "20") (pinfunction "PF8/TIM13_CH1/FSMC_NIOWR/ADC3_IN6_20") (pintype "passive"))
    )
    (net (code "115") (name "unconnected-(U1-PF9{slash}TIM14_CH1{slash}FSMC_CD{slash}ADC3_IN7-Pad21)") (class "Default")
      (node (ref "U1") (pin "21") (pinfunction "PF9/TIM14_CH1/FSMC_CD/ADC3_IN7_21") (pintype "passive"))
    )
    (net (code "116") (name "unconnected-(U1-PF10{slash}FSMC_INTR{slash}ADC3_IN8-Pad22)") (class "Default")
      (node (ref "U1") (pin "22") (pinfunction "PF10/FSMC_INTR/ADC3_IN8_22") (pintype "passive"))
    )
    (net (code "117") (name "unconnected-(U1-PF11{slash}DCMI_D12-Pad49)") (class "Default")
      (node (ref "U1") (pin "49") (pinfunction "PF11/DCMI_D12_49") (pintype "passive"))
    )
    (net (code "118") (name "unconnected-(U1-PF12{slash}FSMC_A6-Pad50)") (class "Default")
      (node (ref "U1") (pin "50") (pinfunction "PF12/FSMC_A6_50") (pintype "passive"))
    )
    (net (code "119") (name "unconnected-(U1-PF13{slash}FSMC_A7-Pad53)") (class "Default")
      (node (ref "U1") (pin "53") (pinfunction "PF13/FSMC_A7_53") (pintype "passive"))
    )
    (net (code "120") (name "unconnected-(U1-PF14{slash}FSMC_A8-Pad54)") (class "Default")
      (node (ref "U1") (pin "54") (pinfunction "PF14/FSMC_A8_54") (pintype "passive"))
    )
    (net (code "121") (name "unconnected-(U1-PF15{slash}FSMC_A9-Pad55)") (class "Default")
      (node (ref "U1") (pin "55") (pinfunction "PF15/FSMC_A9_55") (pintype "passive"))
    )
    (net (code "122") (name "unconnected-(U1-PG2{slash}FSMC_A12-Pad87)") (class "Default")
      (node (ref "U1") (pin "87") (pinfunction "PG2/FSMC_A12_87") (pintype "passive"))
    )
    (net (code "123") (name "unconnected-(U1-PG3{slash}FSMC_A13-Pad88)") (class "Default")
      (node (ref "U1") (pin "88") (pinfunction "PG3/FSMC_A13_88") (pintype "passive"))
    )
    (net (code "124") (name "unconnected-(U1-PG4{slash}FSMC_A14-Pad89)") (class "Default")
      (node (ref "U1") (pin "89") (pinfunction "PG4/FSMC_A14_89") (pintype "passive"))
    )
    (net (code "125") (name "unconnected-(U1-PG5{slash}FSMC_A15-Pad90)") (class "Default")
      (node (ref "U1") (pin "90") (pinfunction "PG5/FSMC_A15_90") (pintype "passive"))
    )
    (net (code "126") (name "unconnected-(U1-PG6{slash}FSMC_INT2-Pad91)") (class "Default")
      (node (ref "U1") (pin "91") (pinfunction "PG6/FSMC_INT2_91") (pintype "passive"))
    )
    (net (code "127") (name "unconnected-(U1-PG7{slash}FSMC_INT3{slash}U6_CK-Pad92)") (class "Default")
      (node (ref "U1") (pin "92") (pinfunction "PG7/FSMC_INT3/U6_CK_92") (pintype "passive"))
    )
    (net (code "128") (name "unconnected-(U1-PG8{slash}U6_RTS{slash}ETH_PPS_OUT-Pad93)") (class "Default")
      (node (ref "U1") (pin "93") (pinfunction "PG8/U6_RTS/ETH_PPS_OUT_93") (pintype "passive"))
    )
  )
)
